# grbl-board.net
KiCad netlist of a schematic drawn in EAGLE
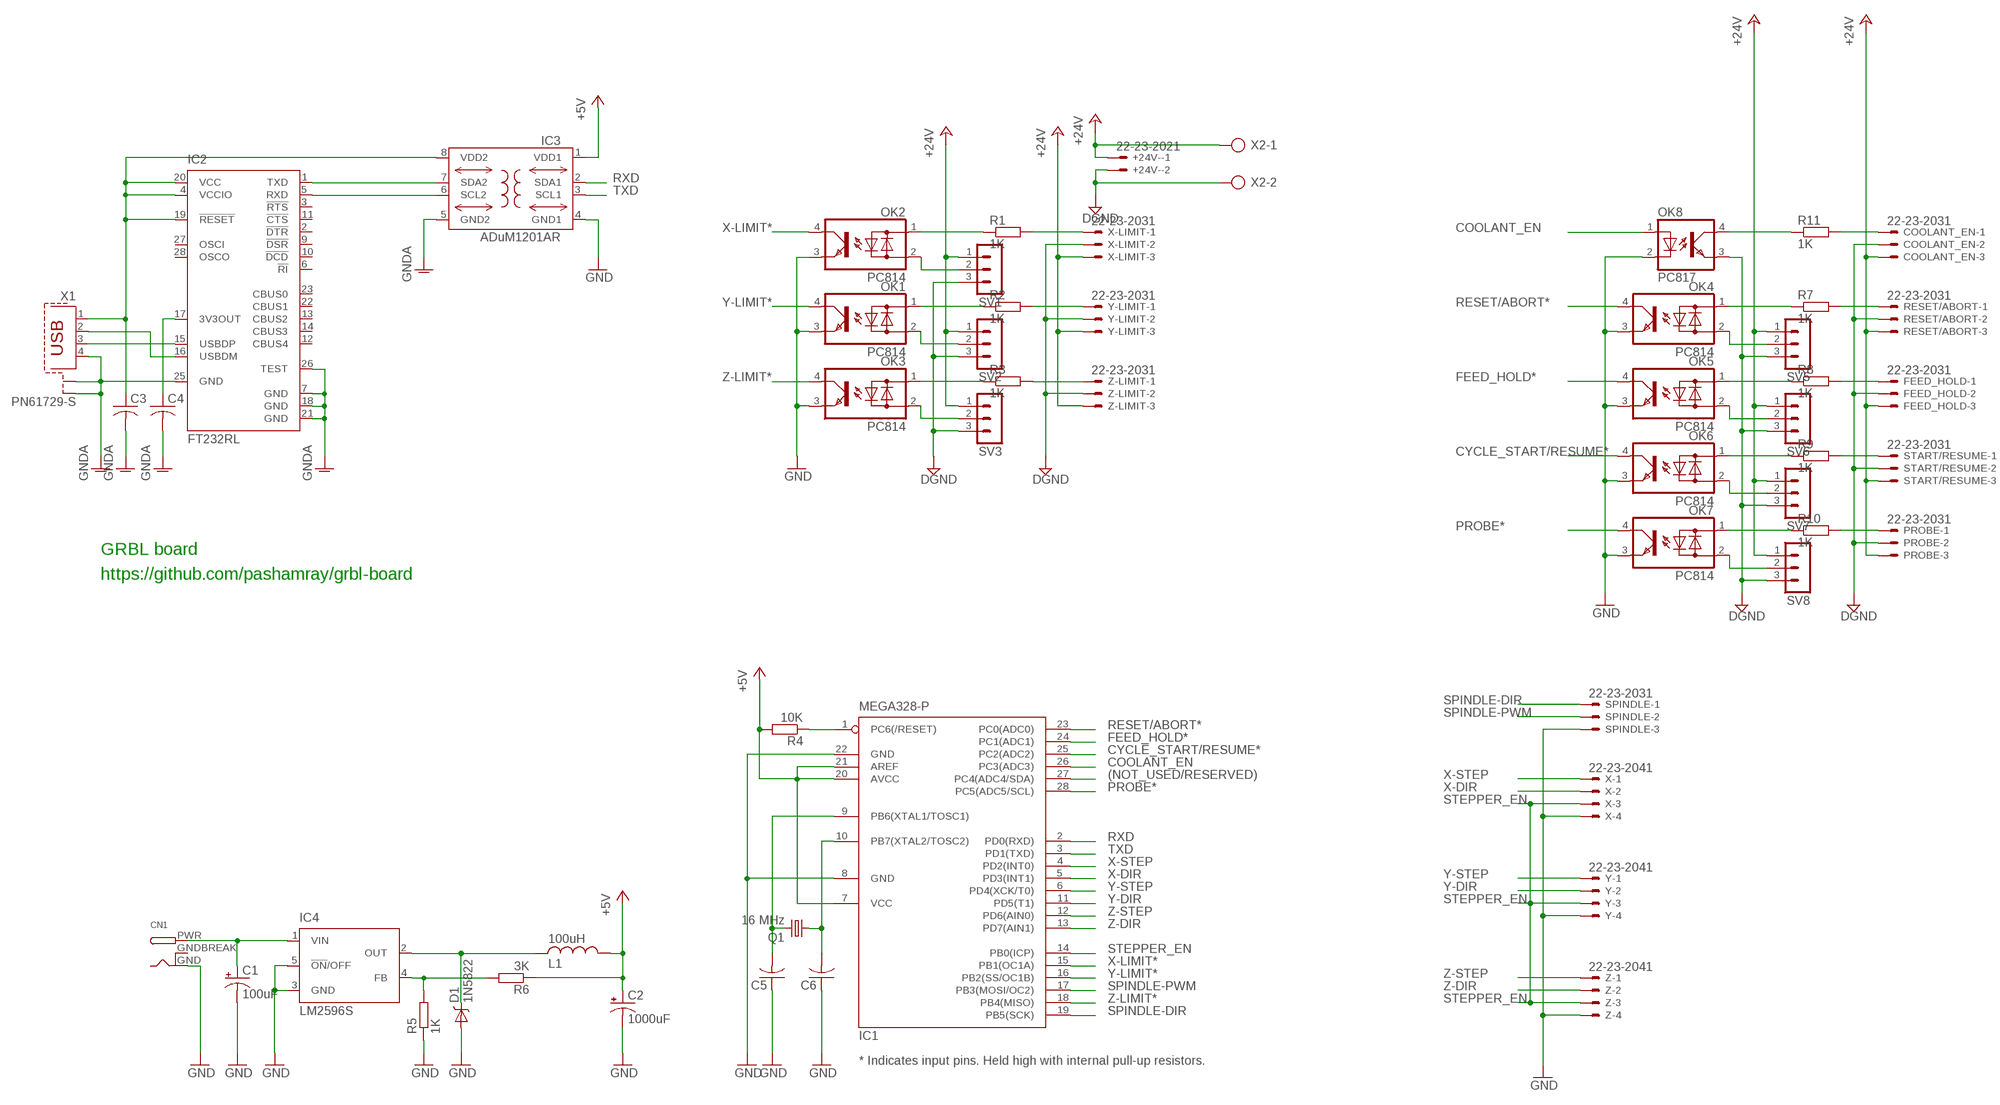
[diagram p0: schematic, sheet 1]

(export (version "E")
  (design (tool "Eeschema 10.0.6"))
  (components
    (comp (ref "+24V-")
      (value "22-23-2021")
      (footprint "eagle-import:22-23-2021")
      (fields (field (name "MF") "MOLEX"))
      (libsource (lib "eagle-import") (part "22-23-2021"))
    )
    (comp (ref "C1")
      (value "100uF")
      (footprint "eagle-import:E5-6")
      (libsource (lib "eagle-import") (part "CPOL-USE5-6"))
    )
    (comp (ref "C2")
      (value "1000uF")
      (footprint "eagle-import:E5-10,5")
      (libsource (lib "eagle-import") (part "CPOL-USE5-10.5"))
    )
    (comp (ref "C3")
      (value "C-USC0805K")
      (footprint "eagle-import:C0805K")
      (libsource (lib "eagle-import") (part "C-USC0805K"))
    )
    (comp (ref "C4")
      (value "C-USC0805K")
      (footprint "eagle-import:C0805K")
      (libsource (lib "eagle-import") (part "C-USC0805K"))
    )
    (comp (ref "C5")
      (value "C-USC0805K")
      (footprint "eagle-import:C0805K")
      (libsource (lib "eagle-import") (part "C-USC0805K"))
    )
    (comp (ref "C6")
      (value "C-USC0805K")
      (footprint "eagle-import:C0805K")
      (libsource (lib "eagle-import") (part "C-USC0805K"))
    )
    (comp (ref "CN1")
      (value "DCBARRELPTH")
      (footprint "eagle-import:DCJACK_2MM_PTH")
      (libsource (lib "eagle-import") (part "DCBARRELPTH"))
    )
    (comp (ref "COOLANT_EN")
      (value "22-23-2031")
      (footprint "eagle-import:22-23-2031")
      (fields (field (name "MF") "MOLEX"))
      (libsource (lib "eagle-import") (part "22-23-2031"))
    )
    (comp (ref "D1")
      (value "1N5822")
      (footprint "eagle-import:SMA-DIODE")
      (libsource (lib "eagle-import") (part "DIODE-SCHOTTKY_"))
    )
    (comp (ref "FEED_HOLD")
      (value "22-23-2031")
      (footprint "eagle-import:22-23-2031")
      (fields (field (name "MF") "MOLEX"))
      (libsource (lib "eagle-import") (part "22-23-2031"))
    )
    (comp (ref "IC1")
      (value "MEGA328-P")
      (footprint "eagle-import:DIL28-3")
      (libsource (lib "eagle-import") (part "MEGA8-P"))
    )
    (comp (ref "IC2")
      (value "FT232RL")
      (footprint "eagle-import:SSOP28")
      (libsource (lib "eagle-import") (part "FT232RL"))
    )
    (comp (ref "IC3")
      (value "ADuM1201AR")
      (footprint "eagle-import:SO8-COOL")
      (libsource (lib "eagle-import") (part "ADUM1250"))
    )
    (comp (ref "IC4")
      (value "LM2596S")
      (footprint "eagle-import:TO263-5")
      (fields (field (name "MF") "NATIONAL SEMICONDUCTOR") (field (name "MPN") "LM2596S-ADJ/NOPB"))
      (libsource (lib "eagle-import") (part "LM2596S"))
    )
    (comp (ref "L1")
      (value "100uH")
      (footprint "eagle-import:1800R")
      (libsource (lib "eagle-import") (part "L1800R"))
    )
    (comp (ref "OK1")
      (value "PC814")
      (footprint "eagle-import:DIL04")
      (libsource (lib "eagle-import") (part "PC814"))
    )
    (comp (ref "OK2")
      (value "PC814")
      (footprint "eagle-import:DIL04")
      (libsource (lib "eagle-import") (part "PC814"))
    )
    (comp (ref "OK3")
      (value "PC814")
      (footprint "eagle-import:DIL04")
      (libsource (lib "eagle-import") (part "PC814"))
    )
    (comp (ref "OK4")
      (value "PC814")
      (footprint "eagle-import:DIL04")
      (libsource (lib "eagle-import") (part "PC814"))
    )
    (comp (ref "OK5")
      (value "PC814")
      (footprint "eagle-import:DIL04")
      (libsource (lib "eagle-import") (part "PC814"))
    )
    (comp (ref "OK6")
      (value "PC814")
      (footprint "eagle-import:DIL04")
      (libsource (lib "eagle-import") (part "PC814"))
    )
    (comp (ref "OK7")
      (value "PC814")
      (footprint "eagle-import:DIL04")
      (libsource (lib "eagle-import") (part "PC814"))
    )
    (comp (ref "OK8")
      (value "PC817")
      (footprint "eagle-import:DIL04")
      (fields (field (name "MPN") "PC817X4J000F"))
      (libsource (lib "eagle-import") (part "PC817"))
    )
    (comp (ref "PROBE")
      (value "22-23-2031")
      (footprint "eagle-import:22-23-2031")
      (fields (field (name "MF") "MOLEX"))
      (libsource (lib "eagle-import") (part "22-23-2031"))
    )
    (comp (ref "Q1")
      (value "16 MHz")
      (footprint "eagle-import:HC49_S")
      (libsource (lib "eagle-import") (part "CRYSTALHC49S"))
    )
    (comp (ref "R1")
      (value "1K")
      (footprint "eagle-import:M0805")
      (libsource (lib "eagle-import") (part "R-EU_M0805"))
    )
    (comp (ref "R2")
      (value "1K")
      (footprint "eagle-import:M0805")
      (libsource (lib "eagle-import") (part "R-EU_M0805"))
    )
    (comp (ref "R3")
      (value "1K")
      (footprint "eagle-import:M0805")
      (libsource (lib "eagle-import") (part "R-EU_M0805"))
    )
    (comp (ref "R4")
      (value "10K")
      (footprint "eagle-import:M0805")
      (libsource (lib "eagle-import") (part "R-EU_M0805"))
    )
    (comp (ref "R5")
      (value "1K")
      (footprint "eagle-import:M0805")
      (libsource (lib "eagle-import") (part "R-EU_M0805"))
    )
    (comp (ref "R6")
      (value "3K")
      (footprint "eagle-import:M0805")
      (libsource (lib "eagle-import") (part "R-EU_M0805"))
    )
    (comp (ref "R7")
      (value "1K")
      (footprint "eagle-import:M0805")
      (libsource (lib "eagle-import") (part "R-EU_M0805"))
    )
    (comp (ref "R8")
      (value "1K")
      (footprint "eagle-import:M0805")
      (libsource (lib "eagle-import") (part "R-EU_M0805"))
    )
    (comp (ref "R9")
      (value "1K")
      (footprint "eagle-import:M0805")
      (libsource (lib "eagle-import") (part "R-EU_M0805"))
    )
    (comp (ref "R10")
      (value "1K")
      (footprint "eagle-import:M0805")
      (libsource (lib "eagle-import") (part "R-EU_M0805"))
    )
    (comp (ref "R11")
      (value "1K")
      (footprint "eagle-import:M0805")
      (libsource (lib "eagle-import") (part "R-EU_M0805"))
    )
    (comp (ref "RESET/ABORT")
      (value "22-23-2031")
      (footprint "eagle-import:22-23-2031")
      (fields (field (name "MF") "MOLEX"))
      (libsource (lib "eagle-import") (part "22-23-2031"))
    )
    (comp (ref "SPINDLE")
      (value "22-23-2031")
      (footprint "eagle-import:22-23-2031")
      (fields (field (name "MF") "MOLEX"))
      (libsource (lib "eagle-import") (part "22-23-2031"))
    )
    (comp (ref "START/RESUME")
      (value "22-23-2031")
      (footprint "eagle-import:22-23-2031")
      (fields (field (name "MF") "MOLEX"))
      (libsource (lib "eagle-import") (part "22-23-2031"))
    )
    (comp (ref "SV1")
      (value "MA03-1")
      (footprint "eagle-import:MA03-1")
      (libsource (lib "eagle-import") (part "MA03-1"))
    )
    (comp (ref "SV2")
      (value "MA03-1")
      (footprint "eagle-import:MA03-1")
      (libsource (lib "eagle-import") (part "MA03-1"))
    )
    (comp (ref "SV3")
      (value "MA03-1")
      (footprint "eagle-import:MA03-1")
      (libsource (lib "eagle-import") (part "MA03-1"))
    )
    (comp (ref "SV5")
      (value "MA03-1")
      (footprint "eagle-import:MA03-1")
      (libsource (lib "eagle-import") (part "MA03-1"))
    )
    (comp (ref "SV6")
      (value "MA03-1")
      (footprint "eagle-import:MA03-1")
      (libsource (lib "eagle-import") (part "MA03-1"))
    )
    (comp (ref "SV7")
      (value "MA03-1")
      (footprint "eagle-import:MA03-1")
      (libsource (lib "eagle-import") (part "MA03-1"))
    )
    (comp (ref "SV8")
      (value "MA03-1")
      (footprint "eagle-import:MA03-1")
      (libsource (lib "eagle-import") (part "MA03-1"))
    )
    (comp (ref "X")
      (value "22-23-2041")
      (footprint "eagle-import:22-23-2041")
      (fields (field (name "MF") "MOLEX"))
      (libsource (lib "eagle-import") (part "22-23-2041"))
    )
    (comp (ref "X-LIMIT")
      (value "22-23-2031")
      (footprint "eagle-import:22-23-2031")
      (fields (field (name "MF") "MOLEX"))
      (libsource (lib "eagle-import") (part "22-23-2031"))
    )
    (comp (ref "X1")
      (value "PN61729-S")
      (footprint "eagle-import:PN61729-S")
      (libsource (lib "eagle-import") (part "PN61729-S"))
    )
    (comp (ref "X2")
      (value "AK500/2")
      (footprint "eagle-import:AK500_2")
      (libsource (lib "eagle-import") (part "AK500/2"))
    )
    (comp (ref "Y")
      (value "22-23-2041")
      (footprint "eagle-import:22-23-2041")
      (fields (field (name "MF") "MOLEX"))
      (libsource (lib "eagle-import") (part "22-23-2041"))
    )
    (comp (ref "Y-LIMIT")
      (value "22-23-2031")
      (footprint "eagle-import:22-23-2031")
      (fields (field (name "MF") "MOLEX"))
      (libsource (lib "eagle-import") (part "22-23-2031"))
    )
    (comp (ref "Z")
      (value "22-23-2041")
      (footprint "eagle-import:22-23-2041")
      (fields (field (name "MF") "MOLEX"))
      (libsource (lib "eagle-import") (part "22-23-2041"))
    )
    (comp (ref "Z-LIMIT")
      (value "22-23-2031")
      (footprint "eagle-import:22-23-2031")
      (fields (field (name "MF") "MOLEX"))
      (libsource (lib "eagle-import") (part "22-23-2031"))
    )
  )
  (nets
    (net (code "1") (name "+5V") (class "Default")
      (node (ref "C2") (pin "+") (pinfunction "+_+") (pintype "passive"))
      (node (ref "IC1") (pin "20") (pinfunction "AVCC_20") (pintype "power_in"))
      (node (ref "IC1") (pin "21") (pinfunction "AREF_21") (pintype "passive"))
      (node (ref "IC1") (pin "7") (pinfunction "VCC_7") (pintype "power_in"))
      (node (ref "IC3") (pin "1") (pinfunction "VDD1_1") (pintype "power_in"))
      (node (ref "L1") (pin "1") (pinfunction "1_1") (pintype "passive"))
      (node (ref "R4") (pin "2") (pinfunction "2_2") (pintype "passive"))
      (node (ref "R6") (pin "1") (pinfunction "1_1") (pintype "passive"))
    )
    (net (code "2") (name "+24V") (class "Default")
      (node (ref "+24V-") (pin "1") (pinfunction "S_1") (pintype "passive"))
      (node (ref "COOLANT_EN") (pin "3") (pinfunction "S_3") (pintype "passive"))
      (node (ref "FEED_HOLD") (pin "3") (pinfunction "S_3") (pintype "passive"))
      (node (ref "PROBE") (pin "3") (pinfunction "S_3") (pintype "passive"))
      (node (ref "RESET/ABORT") (pin "3") (pinfunction "S_3") (pintype "passive"))
      (node (ref "START/RESUME") (pin "3") (pinfunction "S_3") (pintype "passive"))
      (node (ref "SV1") (pin "1") (pinfunction "1_1") (pintype "passive"))
      (node (ref "SV2") (pin "1") (pinfunction "1_1") (pintype "passive"))
      (node (ref "SV3") (pin "1") (pinfunction "1_1") (pintype "passive"))
      (node (ref "SV5") (pin "1") (pinfunction "1_1") (pintype "passive"))
      (node (ref "SV6") (pin "1") (pinfunction "1_1") (pintype "passive"))
      (node (ref "SV7") (pin "1") (pinfunction "1_1") (pintype "passive"))
      (node (ref "SV8") (pin "1") (pinfunction "1_1") (pintype "passive"))
      (node (ref "X-LIMIT") (pin "3") (pinfunction "S_3") (pintype "passive"))
      (node (ref "X2") (pin "1") (pinfunction "KL_1") (pintype "passive"))
      (node (ref "Y-LIMIT") (pin "3") (pinfunction "S_3") (pintype "passive"))
      (node (ref "Z-LIMIT") (pin "3") (pinfunction "S_3") (pintype "passive"))
    )
    (net (code "3") (name "/(NOT_USED{slash}RESERVED)") (class "Default")
      (node (ref "IC1") (pin "27") (pinfunction "PC4(ADC4/SDA)_27") (pintype "bidirectional"))
    )
    (net (code "4") (name "/COOLANT_EN") (class "Default")
      (node (ref "IC1") (pin "26") (pinfunction "PC3(ADC3)_26") (pintype "bidirectional"))
      (node (ref "OK8") (pin "1") (pinfunction "A_1") (pintype "passive"))
    )
    (net (code "5") (name "/CYCLE_START{slash}RESUME*") (class "Default")
      (node (ref "IC1") (pin "25") (pinfunction "PC2(ADC2)_25") (pintype "bidirectional"))
      (node (ref "OK6") (pin "4") (pinfunction "C_4") (pintype "passive"))
    )
    (net (code "6") (name "/FEED_HOLD*") (class "Default")
      (node (ref "IC1") (pin "24") (pinfunction "PC1(ADC1)_24") (pintype "bidirectional"))
      (node (ref "OK5") (pin "4") (pinfunction "C_4") (pintype "passive"))
    )
    (net (code "7") (name "/GNDBREAK") (class "Default")
      (node (ref "CN1") (pin "GNDBREAK") (pinfunction "GNDBREAK_GNDBREAK") (pintype "power_in"))
    )
    (net (code "8") (name "/PROBE*") (class "Default")
      (node (ref "IC1") (pin "28") (pinfunction "PC5(ADC5/SCL)_28") (pintype "bidirectional"))
      (node (ref "OK7") (pin "4") (pinfunction "C_4") (pintype "passive"))
    )
    (net (code "9") (name "/RESET{slash}ABORT*") (class "Default")
      (node (ref "IC1") (pin "23") (pinfunction "PC0(ADC0)_23") (pintype "bidirectional"))
      (node (ref "OK4") (pin "4") (pinfunction "C_4") (pintype "passive"))
    )
    (net (code "10") (name "/RXD") (class "Default")
      (node (ref "IC1") (pin "2") (pinfunction "PD0(RXD)_2") (pintype "bidirectional"))
      (node (ref "IC3") (pin "2") (pinfunction "SDA1_2") (pintype "bidirectional"))
    )
    (net (code "11") (name "/SPINDLE-DIR") (class "Default")
      (node (ref "IC1") (pin "19") (pinfunction "PB5(SCK)_19") (pintype "bidirectional"))
      (node (ref "SPINDLE") (pin "1") (pinfunction "S_1") (pintype "passive"))
    )
    (net (code "12") (name "/SPINDLE-PWM") (class "Default")
      (node (ref "IC1") (pin "17") (pinfunction "PB3(MOSI/OC2)_17") (pintype "bidirectional"))
      (node (ref "SPINDLE") (pin "2") (pinfunction "S_2") (pintype "passive"))
    )
    (net (code "13") (name "/STEPPER_EN") (class "Default")
      (node (ref "IC1") (pin "14") (pinfunction "PB0(ICP)_14") (pintype "bidirectional"))
      (node (ref "X") (pin "3") (pinfunction "S_3") (pintype "passive"))
      (node (ref "Y") (pin "3") (pinfunction "S_3") (pintype "passive"))
      (node (ref "Z") (pin "3") (pinfunction "S_3") (pintype "passive"))
    )
    (net (code "14") (name "/TXD") (class "Default")
      (node (ref "IC1") (pin "3") (pinfunction "PD1(TXD)_3") (pintype "bidirectional"))
      (node (ref "IC3") (pin "3") (pinfunction "SCL1_3") (pintype "bidirectional"))
    )
    (net (code "15") (name "/X-DIR") (class "Default")
      (node (ref "IC1") (pin "5") (pinfunction "PD3(INT1)_5") (pintype "bidirectional"))
      (node (ref "X") (pin "2") (pinfunction "S_2") (pintype "passive"))
    )
    (net (code "16") (name "/X-LIMIT*") (class "Default")
      (node (ref "IC1") (pin "15") (pinfunction "PB1(OC1A)_15") (pintype "bidirectional"))
      (node (ref "OK2") (pin "4") (pinfunction "C_4") (pintype "passive"))
    )
    (net (code "17") (name "/X-STEP") (class "Default")
      (node (ref "IC1") (pin "4") (pinfunction "PD2(INT0)_4") (pintype "bidirectional"))
      (node (ref "X") (pin "1") (pinfunction "S_1") (pintype "passive"))
    )
    (net (code "18") (name "/Y-DIR") (class "Default")
      (node (ref "IC1") (pin "11") (pinfunction "PD5(T1)_11") (pintype "bidirectional"))
      (node (ref "Y") (pin "2") (pinfunction "S_2") (pintype "passive"))
    )
    (net (code "19") (name "/Y-LIMIT*") (class "Default")
      (node (ref "IC1") (pin "16") (pinfunction "PB2(SS/OC1B)_16") (pintype "bidirectional"))
      (node (ref "OK1") (pin "4") (pinfunction "C_4") (pintype "passive"))
    )
    (net (code "20") (name "/Y-STEP") (class "Default")
      (node (ref "IC1") (pin "6") (pinfunction "PD4(XCK/T0)_6") (pintype "bidirectional"))
      (node (ref "Y") (pin "1") (pinfunction "S_1") (pintype "passive"))
    )
    (net (code "21") (name "/Z-DIR") (class "Default")
      (node (ref "IC1") (pin "13") (pinfunction "PD7(AIN1)_13") (pintype "bidirectional"))
      (node (ref "Z") (pin "2") (pinfunction "S_2") (pintype "passive"))
    )
    (net (code "22") (name "/Z-LIMIT*") (class "Default")
      (node (ref "IC1") (pin "18") (pinfunction "PB4(MISO)_18") (pintype "bidirectional"))
      (node (ref "OK3") (pin "4") (pinfunction "C_4") (pintype "passive"))
    )
    (net (code "23") (name "/Z-STEP") (class "Default")
      (node (ref "IC1") (pin "12") (pinfunction "PD6(AIN0)_12") (pintype "bidirectional"))
      (node (ref "Z") (pin "1") (pinfunction "S_1") (pintype "passive"))
    )
    (net (code "24") (name "DGND") (class "Default")
      (node (ref "+24V-") (pin "2") (pinfunction "S_2") (pintype "passive"))
      (node (ref "COOLANT_EN") (pin "2") (pinfunction "S_2") (pintype "passive"))
      (node (ref "FEED_HOLD") (pin "2") (pinfunction "S_2") (pintype "passive"))
      (node (ref "OK8") (pin "3") (pinfunction "EMIT_3") (pintype "passive"))
      (node (ref "PROBE") (pin "2") (pinfunction "S_2") (pintype "passive"))
      (node (ref "RESET/ABORT") (pin "2") (pinfunction "S_2") (pintype "passive"))
      (node (ref "START/RESUME") (pin "2") (pinfunction "S_2") (pintype "passive"))
      (node (ref "SV1") (pin "3") (pinfunction "3_3") (pintype "passive"))
      (node (ref "SV2") (pin "3") (pinfunction "3_3") (pintype "passive"))
      (node (ref "SV3") (pin "3") (pinfunction "3_3") (pintype "passive"))
      (node (ref "SV5") (pin "3") (pinfunction "3_3") (pintype "passive"))
      (node (ref "SV6") (pin "3") (pinfunction "3_3") (pintype "passive"))
      (node (ref "SV7") (pin "3") (pinfunction "3_3") (pintype "passive"))
      (node (ref "SV8") (pin "3") (pinfunction "3_3") (pintype "passive"))
      (node (ref "X-LIMIT") (pin "2") (pinfunction "S_2") (pintype "passive"))
      (node (ref "X2") (pin "2") (pinfunction "KL_2") (pintype "passive"))
      (node (ref "Y-LIMIT") (pin "2") (pinfunction "S_2") (pintype "passive"))
      (node (ref "Z-LIMIT") (pin "2") (pinfunction "S_2") (pintype "passive"))
    )
    (net (code "25") (name "GND") (class "Default")
      (node (ref "C1") (pin "-") (pinfunction "-_-") (pintype "passive"))
      (node (ref "C2") (pin "-") (pinfunction "-_-") (pintype "passive"))
      (node (ref "C5") (pin "1") (pinfunction "1_1") (pintype "passive"))
      (node (ref "C6") (pin "1") (pinfunction "1_1") (pintype "passive"))
      (node (ref "CN1") (pin "GND") (pinfunction "GND_GND") (pintype "power_in"))
      (node (ref "D1") (pin "A") (pinfunction "A_A") (pintype "passive"))
      (node (ref "IC1") (pin "22") (pinfunction "GND_22") (pintype "power_in"))
      (node (ref "IC1") (pin "8") (pinfunction "GND_8") (pintype "power_in"))
      (node (ref "IC3") (pin "4") (pinfunction "GND1_4") (pintype "power_in"))
      (node (ref "IC4") (pin "3") (pinfunction "GND_3") (pintype "power_in"))
      (node (ref "IC4") (pin "5") (pinfunction "~{ON}/OFF_5") (pintype "input"))
      (node (ref "OK1") (pin "3") (pinfunction "E_3") (pintype "passive"))
      (node (ref "OK2") (pin "3") (pinfunction "E_3") (pintype "passive"))
      (node (ref "OK3") (pin "3") (pinfunction "E_3") (pintype "passive"))
      (node (ref "OK4") (pin "3") (pinfunction "E_3") (pintype "passive"))
      (node (ref "OK5") (pin "3") (pinfunction "E_3") (pintype "passive"))
      (node (ref "OK6") (pin "3") (pinfunction "E_3") (pintype "passive"))
      (node (ref "OK7") (pin "3") (pinfunction "E_3") (pintype "passive"))
      (node (ref "OK8") (pin "2") (pinfunction "C_2") (pintype "passive"))
      (node (ref "R5") (pin "1") (pinfunction "1_1") (pintype "passive"))
      (node (ref "SPINDLE") (pin "3") (pinfunction "S_3") (pintype "passive"))
      (node (ref "X") (pin "4") (pinfunction "S_4") (pintype "passive"))
      (node (ref "Y") (pin "4") (pinfunction "S_4") (pintype "passive"))
      (node (ref "Z") (pin "4") (pinfunction "S_4") (pintype "passive"))
    )
    (net (code "26") (name "GNDA") (class "Default")
      (node (ref "C3") (pin "2") (pinfunction "2_2") (pintype "passive"))
      (node (ref "C4") (pin "2") (pinfunction "2_2") (pintype "passive"))
      (node (ref "IC2") (pin "18") (pinfunction "GND_18") (pintype "power_in"))
      (node (ref "IC2") (pin "21") (pinfunction "GND_21") (pintype "power_in"))
      (node (ref "IC2") (pin "25") (pinfunction "GND_25") (pintype "power_in"))
      (node (ref "IC2") (pin "26") (pinfunction "TEST_26") (pintype "input"))
      (node (ref "IC2") (pin "7") (pinfunction "GND_7") (pintype "power_in"))
      (node (ref "IC3") (pin "5") (pinfunction "GND2_5") (pintype "power_in"))
      (node (ref "X1") (pin "4") (pinfunction "4_4") (pintype "passive"))
      (node (ref "X1") (pin "S1") (pinfunction "S1_S1") (pintype "passive"))
      (node (ref "X1") (pin "S2") (pinfunction "S2_S2") (pintype "passive"))
    )
    (net (code "27") (name "Net-(COOLANT_ENA-S)") (class "Default")
      (node (ref "COOLANT_EN") (pin "1") (pinfunction "S_1") (pintype "passive"))
      (node (ref "R11") (pin "2") (pinfunction "2_2") (pintype "passive"))
    )
    (net (code "28") (name "Net-(FEED_HOLDA-S)") (class "Default")
      (node (ref "FEED_HOLD") (pin "1") (pinfunction "S_1") (pintype "passive"))
      (node (ref "R8") (pin "2") (pinfunction "2_2") (pintype "passive"))
    )
    (net (code "29") (name "Net-(IC1-PB6(XTAL1{slash}TOSC1))") (class "Default")
      (node (ref "C5") (pin "2") (pinfunction "2_2") (pintype "passive"))
      (node (ref "IC1") (pin "9") (pinfunction "PB6(XTAL1/TOSC1)_9") (pintype "bidirectional"))
      (node (ref "Q1") (pin "2") (pinfunction "2_2") (pintype "passive"))
    )
    (net (code "30") (name "Net-(IC1-PB7(XTAL2{slash}TOSC2))") (class "Default")
      (node (ref "C6") (pin "2") (pinfunction "2_2") (pintype "passive"))
      (node (ref "IC1") (pin "10") (pinfunction "PB7(XTAL2/TOSC2)_10") (pintype "bidirectional"))
      (node (ref "Q1") (pin "1") (pinfunction "1_1") (pintype "passive"))
    )
    (net (code "31") (name "Net-(IC1-PC6({slash}RESET))") (class "Default")
      (node (ref "IC1") (pin "1") (pinfunction "PC6(/RESET)_1") (pintype "bidirectional"))
      (node (ref "R4") (pin "1") (pinfunction "1_1") (pintype "passive"))
    )
    (net (code "32") (name "Net-(IC2-3V3OUT)") (class "Default")
      (node (ref "C4") (pin "1") (pinfunction "1_1") (pintype "passive"))
      (node (ref "IC2") (pin "17") (pinfunction "3V3OUT_17") (pintype "output"))
    )
    (net (code "33") (name "Net-(IC2-RXD)") (class "Default")
      (node (ref "IC2") (pin "5") (pinfunction "RXD_5") (pintype "input"))
      (node (ref "IC3") (pin "6") (pinfunction "SCL2_6") (pintype "bidirectional"))
    )
    (net (code "34") (name "Net-(IC2-TXD)") (class "Default")
      (node (ref "IC2") (pin "1") (pinfunction "TXD_1") (pintype "output"))
      (node (ref "IC3") (pin "7") (pinfunction "SDA2_7") (pintype "bidirectional"))
    )
    (net (code "35") (name "Net-(IC2-USBDM)") (class "Default")
      (node (ref "IC2") (pin "16") (pinfunction "USBDM_16") (pintype "bidirectional"))
      (node (ref "X1") (pin "2") (pinfunction "2_2") (pintype "passive"))
    )
    (net (code "36") (name "Net-(IC2-USBDP)") (class "Default")
      (node (ref "IC2") (pin "15") (pinfunction "USBDP_15") (pintype "bidirectional"))
      (node (ref "X1") (pin "3") (pinfunction "3_3") (pintype "passive"))
    )
    (net (code "37") (name "Net-(IC2-VCC)") (class "Default")
      (node (ref "C3") (pin "1") (pinfunction "1_1") (pintype "passive"))
      (node (ref "IC2") (pin "19") (pinfunction "~{RESET}_19") (pintype "input"))
      (node (ref "IC2") (pin "20") (pinfunction "VCC_20") (pintype "power_in"))
      (node (ref "IC2") (pin "4") (pinfunction "VCCIO_4") (pintype "power_in"))
      (node (ref "IC3") (pin "8") (pinfunction "VDD2_8") (pintype "power_in"))
      (node (ref "X1") (pin "1") (pinfunction "1_1") (pintype "passive"))
    )
    (net (code "38") (name "Net-(IC4-FB)") (class "Default")
      (node (ref "IC4") (pin "4") (pinfunction "FB_4") (pintype "input"))
      (node (ref "R5") (pin "2") (pinfunction "2_2") (pintype "passive"))
      (node (ref "R6") (pin "2") (pinfunction "2_2") (pintype "passive"))
    )
    (net (code "39") (name "Net-(IC4-OUT)") (class "Default")
      (node (ref "D1") (pin "C") (pinfunction "C_C") (pintype "passive"))
      (node (ref "IC4") (pin "2") (pinfunction "OUT_2") (pintype "output"))
      (node (ref "L1") (pin "2") (pinfunction "2_2") (pintype "passive"))
    )
    (net (code "40") (name "Net-(IC4-VIN)") (class "Default")
      (node (ref "C1") (pin "+") (pinfunction "+_+") (pintype "passive"))
      (node (ref "CN1") (pin "PWR") (pinfunction "PWR_PWR") (pintype "power_in"))
      (node (ref "IC4") (pin "1") (pinfunction "VIN_1") (pintype "input"))
    )
    (net (code "41") (name "Net-(OK1-AC1)") (class "Default")
      (node (ref "OK1") (pin "1") (pinfunction "AC1_1") (pintype "passive"))
      (node (ref "R2") (pin "1") (pinfunction "1_1") (pintype "passive"))
    )
    (net (code "42") (name "Net-(OK1-AC2)") (class "Default")
      (node (ref "OK1") (pin "2") (pinfunction "AC2_2") (pintype "passive"))
      (node (ref "SV2") (pin "2") (pinfunction "2_2") (pintype "passive"))
    )
    (net (code "43") (name "Net-(OK2-AC1)") (class "Default")
      (node (ref "OK2") (pin "1") (pinfunction "AC1_1") (pintype "passive"))
      (node (ref "R1") (pin "1") (pinfunction "1_1") (pintype "passive"))
    )
    (net (code "44") (name "Net-(OK2-AC2)") (class "Default")
      (node (ref "OK2") (pin "2") (pinfunction "AC2_2") (pintype "passive"))
      (node (ref "SV1") (pin "2") (pinfunction "2_2") (pintype "passive"))
    )
    (net (code "45") (name "Net-(OK3-AC1)") (class "Default")
      (node (ref "OK3") (pin "1") (pinfunction "AC1_1") (pintype "passive"))
      (node (ref "R3") (pin "1") (pinfunction "1_1") (pintype "passive"))
    )
    (net (code "46") (name "Net-(OK3-AC2)") (class "Default")
      (node (ref "OK3") (pin "2") (pinfunction "AC2_2") (pintype "passive"))
      (node (ref "SV3") (pin "2") (pinfunction "2_2") (pintype "passive"))
    )
    (net (code "47") (name "Net-(OK4-AC1)") (class "Default")
      (node (ref "OK4") (pin "1") (pinfunction "AC1_1") (pintype "passive"))
      (node (ref "R7") (pin "1") (pinfunction "1_1") (pintype "passive"))
    )
    (net (code "48") (name "Net-(OK4-AC2)") (class "Default")
      (node (ref "OK4") (pin "2") (pinfunction "AC2_2") (pintype "passive"))
      (node (ref "SV5") (pin "2") (pinfunction "2_2") (pintype "passive"))
    )
    (net (code "49") (name "Net-(OK5-AC1)") (class "Default")
      (node (ref "OK5") (pin "1") (pinfunction "AC1_1") (pintype "passive"))
      (node (ref "R8") (pin "1") (pinfunction "1_1") (pintype "passive"))
    )
    (net (code "50") (name "Net-(OK5-AC2)") (class "Default")
      (node (ref "OK5") (pin "2") (pinfunction "AC2_2") (pintype "passive"))
      (node (ref "SV6") (pin "2") (pinfunction "2_2") (pintype "passive"))
    )
    (net (code "51") (name "Net-(OK6-AC1)") (class "Default")
      (node (ref "OK6") (pin "1") (pinfunction "AC1_1") (pintype "passive"))
      (node (ref "R9") (pin "1") (pinfunction "1_1") (pintype "passive"))
    )
    (net (code "52") (name "Net-(OK6-AC2)") (class "Default")
      (node (ref "OK6") (pin "2") (pinfunction "AC2_2") (pintype "passive"))
      (node (ref "SV7") (pin "2") (pinfunction "2_2") (pintype "passive"))
    )
    (net (code "53") (name "Net-(OK7-AC1)") (class "Default")
      (node (ref "OK7") (pin "1") (pinfunction "AC1_1") (pintype "passive"))
      (node (ref "R10") (pin "1") (pinfunction "1_1") (pintype "passive"))
    )
    (net (code "54") (name "Net-(OK7-AC2)") (class "Default")
      (node (ref "OK7") (pin "2") (pinfunction "AC2_2") (pintype "passive"))
      (node (ref "SV8") (pin "2") (pinfunction "2_2") (pintype "passive"))
    )
    (net (code "55") (name "Net-(OK8-COL)") (class "Default")
      (node (ref "OK8") (pin "4") (pinfunction "COL_4") (pintype "passive"))
      (node (ref "R11") (pin "1") (pinfunction "1_1") (pintype "passive"))
    )
    (net (code "56") (name "Net-(PROBEA-S)") (class "Default")
      (node (ref "PROBE") (pin "1") (pinfunction "S_1") (pintype "passive"))
      (node (ref "R10") (pin "2") (pinfunction "2_2") (pintype "passive"))
    )
    (net (code "57") (name "Net-(RESET/ABORTA-S)") (class "Default")
      (node (ref "R7") (pin "2") (pinfunction "2_2") (pintype "passive"))
      (node (ref "RESET/ABORT") (pin "1") (pinfunction "S_1") (pintype "passive"))
    )
    (net (code "58") (name "Net-(START/RESUMEA-S)") (class "Default")
      (node (ref "R9") (pin "2") (pinfunction "2_2") (pintype "passive"))
      (node (ref "START/RESUME") (pin "1") (pinfunction "S_1") (pintype "passive"))
    )
    (net (code "59") (name "Net-(X-LIMITA-S)") (class "Default")
      (node (ref "R1") (pin "2") (pinfunction "2_2") (pintype "passive"))
      (node (ref "X-LIMIT") (pin "1") (pinfunction "S_1") (pintype "passive"))
    )
    (net (code "60") (name "Net-(Y-LIMITA-S)") (class "Default")
      (node (ref "R2") (pin "2") (pinfunction "2_2") (pintype "passive"))
      (node (ref "Y-LIMIT") (pin "1") (pinfunction "S_1") (pintype "passive"))
    )
    (net (code "61") (name "Net-(Z-LIMITA-S)") (class "Default")
      (node (ref "R3") (pin "2") (pinfunction "2_2") (pintype "passive"))
      (node (ref "Z-LIMIT") (pin "1") (pinfunction "S_1") (pintype "passive"))
    )
    (net (code "62") (name "unconnected-(IC2-CBUS0-Pad23)") (class "Default")
      (node (ref "IC2") (pin "23") (pinfunction "CBUS0_23") (pintype "bidirectional"))
    )
    (net (code "63") (name "unconnected-(IC2-CBUS1-Pad22)") (class "Default")
      (node (ref "IC2") (pin "22") (pinfunction "CBUS1_22") (pintype "bidirectional"))
    )
    (net (code "64") (name "unconnected-(IC2-CBUS2-Pad13)") (class "Default")
      (node (ref "IC2") (pin "13") (pinfunction "CBUS2_13") (pintype "bidirectional"))
    )
    (net (code "65") (name "unconnected-(IC2-CBUS3-Pad14)") (class "Default")
      (node (ref "IC2") (pin "14") (pinfunction "CBUS3_14") (pintype "bidirectional"))
    )
    (net (code "66") (name "unconnected-(IC2-CBUS4-Pad12)") (class "Default")
      (node (ref "IC2") (pin "12") (pinfunction "CBUS4_12") (pintype "bidirectional"))
    )
    (net (code "67") (name "unconnected-(IC2-OSCI-Pad27)") (class "Default")
      (node (ref "IC2") (pin "27") (pinfunction "OSCI_27") (pintype "input"))
    )
    (net (code "68") (name "unconnected-(IC2-OSCO-Pad28)") (class "Default")
      (node (ref "IC2") (pin "28") (pinfunction "OSCO_28") (pintype "output"))
    )
    (net (code "69") (name "unconnected-(IC2-~{CTS}-Pad11)") (class "Default")
      (node (ref "IC2") (pin "11") (pinfunction "~{CTS}_11") (pintype "input"))
    )
    (net (code "70") (name "unconnected-(IC2-~{DCD}-Pad10)") (class "Default")
      (node (ref "IC2") (pin "10") (pinfunction "~{DCD}_10") (pintype "input"))
    )
    (net (code "71") (name "unconnected-(IC2-~{DSR}-Pad9)") (class "Default")
      (node (ref "IC2") (pin "9") (pinfunction "~{DSR}_9") (pintype "input"))
    )
    (net (code "72") (name "unconnected-(IC2-~{DTR}-Pad2)") (class "Default")
      (node (ref "IC2") (pin "2") (pinfunction "~{DTR}_2") (pintype "output"))
    )
    (net (code "73") (name "unconnected-(IC2-~{RI}-Pad6)") (class "Default")
      (node (ref "IC2") (pin "6") (pinfunction "~{RI}_6") (pintype "input"))
    )
    (net (code "74") (name "unconnected-(IC2-~{RTS}-Pad3)") (class "Default")
      (node (ref "IC2") (pin "3") (pinfunction "~{RTS}_3") (pintype "output"))
    )
  )
)
